# PIC.net
KiCad netlist of a schematic drawn in Altium Designer
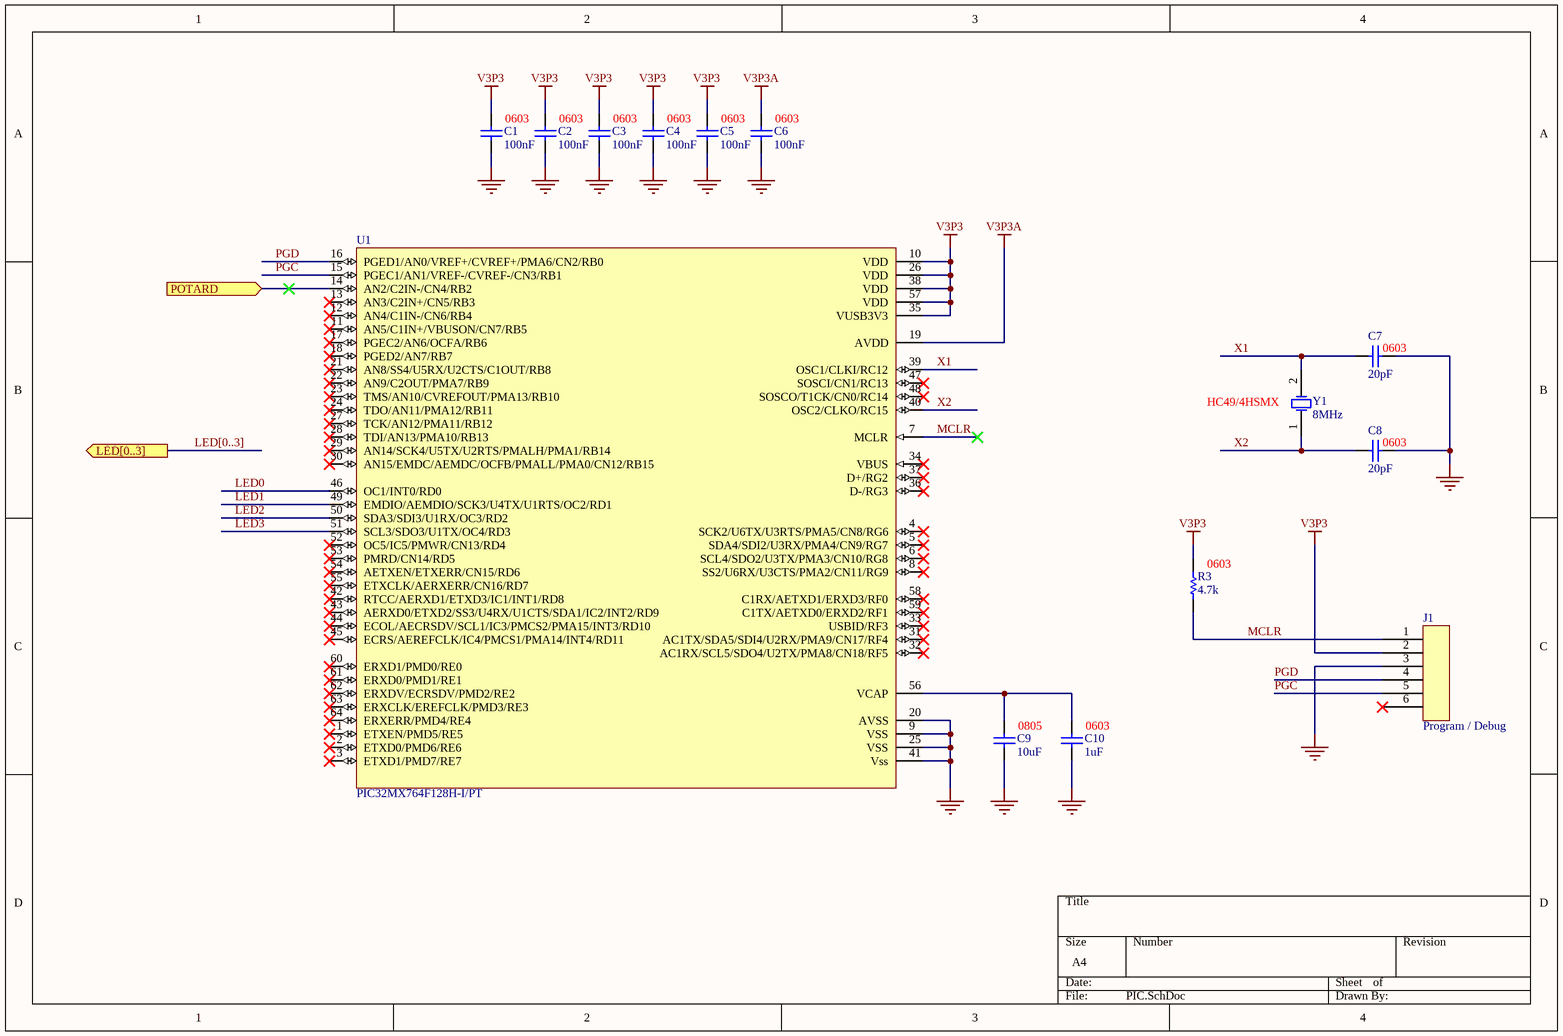
[diagram p0: PIC.SchDoc]

(export (version "E")
  (design (tool "Eeschema 10.0.6"))
  (components
    (comp (ref "C1")
      (value "100nF")
      (footprint "0603")
      (description "Capacitor")
      (fields (field (name "PUBLISHER") "Altium Limited"))
      (libsource (lib "Miscellaneous Devices") (part "Cap"))
    )
    (comp (ref "C2")
      (value "100nF")
      (footprint "0603")
      (description "Capacitor")
      (fields (field (name "PUBLISHER") "Altium Limited"))
      (libsource (lib "Miscellaneous Devices") (part "Cap"))
    )
    (comp (ref "C3")
      (value "100nF")
      (footprint "0603")
      (description "Capacitor")
      (fields (field (name "PUBLISHER") "Altium Limited"))
      (libsource (lib "Miscellaneous Devices") (part "Cap"))
    )
    (comp (ref "C4")
      (value "100nF")
      (footprint "0603")
      (description "Capacitor")
      (fields (field (name "PUBLISHER") "Altium Limited"))
      (libsource (lib "Miscellaneous Devices") (part "Cap"))
    )
    (comp (ref "C5")
      (value "100nF")
      (footprint "0603")
      (description "Capacitor")
      (fields (field (name "PUBLISHER") "Altium Limited"))
      (libsource (lib "Miscellaneous Devices") (part "Cap"))
    )
    (comp (ref "C6")
      (value "100nF")
      (footprint "0603")
      (description "Capacitor")
      (fields (field (name "PUBLISHER") "Altium Limited"))
      (libsource (lib "Miscellaneous Devices") (part "Cap"))
    )
    (comp (ref "C7")
      (value "20pF")
      (footprint "0603")
      (description "Capacitor")
      (fields (field (name "PUBLISHER") "Altium Limited"))
      (libsource (lib "Miscellaneous Devices") (part "Cap"))
    )
    (comp (ref "C8")
      (value "20pF")
      (footprint "0603")
      (description "Capacitor")
      (fields (field (name "PUBLISHER") "Altium Limited"))
      (libsource (lib "Miscellaneous Devices") (part "Cap"))
    )
    (comp (ref "C9")
      (value "10uF")
      (footprint "0805")
      (description "Capacitor")
      (fields (field (name "PUBLISHER") "Altium Limited"))
      (libsource (lib "Miscellaneous Devices") (part "Cap"))
    )
    (comp (ref "C10")
      (value "1uF")
      (footprint "0603")
      (description "Capacitor")
      (fields (field (name "PUBLISHER") "Altium Limited"))
      (libsource (lib "Miscellaneous Devices") (part "Cap"))
    )
    (comp (ref "J1")
      (value "Program / Debug")
      (footprint "TP2_PcbLib:RJ12_90")
      (description "RJ11")
      (libsource (lib "Program_Debug") (part "Program / Debug"))
    )
    (comp (ref "R3")
      (value "4.7k")
      (footprint "0603")
      (description "Resistor")
      (fields (field (name "PUBLISHER") "Altium Limited"))
      (libsource (lib "Miscellaneous Devices") (part "Res1"))
    )
    (comp (ref "U1")
      (value "PIC32MX764F128H-I/PT")
      (footprint "TP2_PcbLib:QFP50P1200X1200X120-64")
      (description "PIC32MX764F128H")
      (libsource (lib "TP2") (part "PIC32MX764F128H-I/PT"))
    )
    (comp (ref "Y1")
      (value "8MHz")
      (footprint "HC49/4HSMX")
      (description "Crystal Oscillator")
      (fields (field (name "PUBLISHER") "Altium Limited"))
      (libsource (lib "Miscellaneous Devices") (part "XTAL"))
    )
  )
  (nets
    (net (code "1") (name "/LED0") (class "Default")
      (node (ref "U1") (pin "46") (pinfunction "OC1/INT0/RD0_46") (pintype "bidirectional"))
    )
    (net (code "2") (name "/LED1") (class "Default")
      (node (ref "U1") (pin "49") (pinfunction "EMDIO/AEMDIO/SCK3/U4TX/U1RTS/OC2/RD1_49") (pintype "bidirectional"))
    )
    (net (code "3") (name "/LED2") (class "Default")
      (node (ref "U1") (pin "50") (pinfunction "SDA3/SDI3/U1RX/OC3/RD2_50") (pintype "bidirectional"))
    )
    (net (code "4") (name "/LED3") (class "Default")
      (node (ref "U1") (pin "51") (pinfunction "SCL3/SDO3/U1TX/OC4/RD3_51") (pintype "bidirectional"))
    )
    (net (code "6") (name "/MCLR") (class "Default")
      (node (ref "J1") (pin "1") (pinfunction "*_1") (pintype "passive"))
      (node (ref "R3") (pin "2") (pinfunction "2_2") (pintype "passive"))
      (node (ref "U1") (pin "7") (pinfunction "MCLR_7") (pintype "input"))
    )
    (net (code "7") (name "/PGC") (class "Default")
      (node (ref "J1") (pin "5") (pinfunction "5_5") (pintype "passive"))
      (node (ref "U1") (pin "15") (pinfunction "PGEC1/AN1/VREF-/CVREF-/CN3/RB1_15") (pintype "bidirectional"))
    )
    (net (code "8") (name "/PGD") (class "Default")
      (node (ref "J1") (pin "4") (pinfunction "4_4") (pintype "passive"))
      (node (ref "U1") (pin "16") (pinfunction "PGED1/AN0/VREF+/CVREF+/PMA6/CN2/RB0_16") (pintype "bidirectional"))
    )
    (net (code "9") (name "/POTARD") (class "Default")
      (node (ref "U1") (pin "14") (pinfunction "AN2/C2IN-/CN4/RB2_14") (pintype "bidirectional+no_connect"))
    )
    (net (code "10") (name "/X1") (class "Default")
      (node (ref "C7") (pin "2") (pinfunction "2_2") (pintype "passive"))
      (node (ref "U1") (pin "39") (pinfunction "OSC1/CLKI/RC12_39") (pintype "bidirectional"))
      (node (ref "Y1") (pin "2") (pinfunction "OSC2_2") (pintype "passive"))
    )
    (net (code "11") (name "/X2") (class "Default")
      (node (ref "C8") (pin "2") (pinfunction "2_2") (pintype "passive"))
      (node (ref "U1") (pin "40") (pinfunction "OSC2/CLKO/RC15_40") (pintype "bidirectional"))
      (node (ref "Y1") (pin "1") (pinfunction "OSC1_1") (pintype "passive"))
    )
    (net (code "12") (name "GND") (class "Default")
      (node (ref "C1") (pin "1") (pinfunction "1_1") (pintype "passive"))
      (node (ref "C10") (pin "1") (pinfunction "1_1") (pintype "passive"))
      (node (ref "C2") (pin "1") (pinfunction "1_1") (pintype "passive"))
      (node (ref "C3") (pin "1") (pinfunction "1_1") (pintype "passive"))
      (node (ref "C4") (pin "1") (pinfunction "1_1") (pintype "passive"))
      (node (ref "C5") (pin "1") (pinfunction "1_1") (pintype "passive"))
      (node (ref "C6") (pin "1") (pinfunction "1_1") (pintype "passive"))
      (node (ref "C7") (pin "1") (pinfunction "1_1") (pintype "passive"))
      (node (ref "C8") (pin "1") (pinfunction "1_1") (pintype "passive"))
      (node (ref "C9") (pin "1") (pinfunction "1_1") (pintype "passive"))
      (node (ref "J1") (pin "3") (pinfunction "3_3") (pintype "passive"))
      (node (ref "U1") (pin "20") (pinfunction "AVSS_20") (pintype "passive"))
      (node (ref "U1") (pin "25") (pinfunction "VSS_25") (pintype "passive"))
      (node (ref "U1") (pin "41") (pinfunction "Vss_41") (pintype "passive"))
      (node (ref "U1") (pin "9") (pinfunction "VSS_9") (pintype "passive"))
    )
    (net (code "13") (name "Net-(U1-VCAP)") (class "Default")
      (node (ref "C10") (pin "2") (pinfunction "2_2") (pintype "passive"))
      (node (ref "C9") (pin "2") (pinfunction "2_2") (pintype "passive"))
      (node (ref "U1") (pin "56") (pinfunction "VCAP_56") (pintype "passive"))
    )
    (net (code "14") (name "V3P3") (class "Default")
      (node (ref "C1") (pin "2") (pinfunction "2_2") (pintype "passive"))
      (node (ref "C2") (pin "2") (pinfunction "2_2") (pintype "passive"))
      (node (ref "C3") (pin "2") (pinfunction "2_2") (pintype "passive"))
      (node (ref "C4") (pin "2") (pinfunction "2_2") (pintype "passive"))
      (node (ref "C5") (pin "2") (pinfunction "2_2") (pintype "passive"))
      (node (ref "J1") (pin "2") (pinfunction "2_2") (pintype "passive"))
      (node (ref "R3") (pin "1") (pinfunction "1_1") (pintype "passive"))
      (node (ref "U1") (pin "10") (pinfunction "VDD_10") (pintype "passive"))
      (node (ref "U1") (pin "26") (pinfunction "VDD_26") (pintype "passive"))
      (node (ref "U1") (pin "35") (pinfunction "VUSB3V3_35") (pintype "passive"))
      (node (ref "U1") (pin "38") (pinfunction "VDD_38") (pintype "passive"))
      (node (ref "U1") (pin "57") (pinfunction "VDD_57") (pintype "passive"))
    )
    (net (code "15") (name "V3P3A") (class "Default")
      (node (ref "C6") (pin "2") (pinfunction "2_2") (pintype "passive"))
      (node (ref "U1") (pin "19") (pinfunction "AVDD_19") (pintype "passive"))
    )
    (net (code "16") (name "unconnected-(J1-Pad6)") (class "Default")
      (node (ref "J1") (pin "6") (pinfunction "6_6") (pintype "passive+no_connect"))
    )
    (net (code "17") (name "unconnected-(U1-AC1RX{slash}SCL5{slash}SDO4{slash}U2TX{slash}PMA8{slash}CN18{slash}RF5-Pad32)") (class "Default")
      (node (ref "U1") (pin "32") (pinfunction "AC1RX/SCL5/SDO4/U2TX/PMA8/CN18/RF5_32") (pintype "bidirectional+no_connect"))
    )
    (net (code "18") (name "unconnected-(U1-AC1TX{slash}SDA5{slash}SDI4{slash}U2RX{slash}PMA9{slash}CN17{slash}RF4-Pad31)") (class "Default")
      (node (ref "U1") (pin "31") (pinfunction "AC1TX/SDA5/SDI4/U2RX/PMA9/CN17/RF4_31") (pintype "bidirectional+no_connect"))
    )
    (net (code "19") (name "unconnected-(U1-AERXD0{slash}ETXD2{slash}SS3{slash}U4RX{slash}U1CTS{slash}SDA1{slash}IC2{slash}INT2{slash}RD9-Pad43)") (class "Default")
      (node (ref "U1") (pin "43") (pinfunction "AERXD0/ETXD2/SS3/U4RX/U1CTS/SDA1/IC2/INT2/RD9_43") (pintype "bidirectional+no_connect"))
    )
    (net (code "20") (name "unconnected-(U1-AETXEN{slash}ETXERR{slash}CN15{slash}RD6-Pad54)") (class "Default")
      (node (ref "U1") (pin "54") (pinfunction "AETXEN/ETXERR/CN15/RD6_54") (pintype "bidirectional+no_connect"))
    )
    (net (code "21") (name "unconnected-(U1-AN3{slash}C2IN+{slash}CN5{slash}RB3-Pad13)") (class "Default")
      (node (ref "U1") (pin "13") (pinfunction "AN3/C2IN+/CN5/RB3_13") (pintype "bidirectional+no_connect"))
    )
    (net (code "22") (name "unconnected-(U1-AN4{slash}C1IN-{slash}CN6{slash}RB4-Pad12)") (class "Default")
      (node (ref "U1") (pin "12") (pinfunction "AN4/C1IN-/CN6/RB4_12") (pintype "bidirectional+no_connect"))
    )
    (net (code "23") (name "unconnected-(U1-AN5{slash}C1IN+{slash}VBUSON{slash}CN7{slash}RB5-Pad11)") (class "Default")
      (node (ref "U1") (pin "11") (pinfunction "AN5/C1IN+/VBUSON/CN7/RB5_11") (pintype "bidirectional+no_connect"))
    )
    (net (code "24") (name "unconnected-(U1-AN8{slash}SS4{slash}U5RX{slash}U2CTS{slash}C1OUT{slash}RB8-Pad21)") (class "Default")
      (node (ref "U1") (pin "21") (pinfunction "AN8/SS4/U5RX/U2CTS/C1OUT/RB8_21") (pintype "bidirectional+no_connect"))
    )
    (net (code "25") (name "unconnected-(U1-AN9{slash}C2OUT{slash}PMA7{slash}RB9-Pad22)") (class "Default")
      (node (ref "U1") (pin "22") (pinfunction "AN9/C2OUT/PMA7/RB9_22") (pintype "bidirectional+no_connect"))
    )
    (net (code "26") (name "unconnected-(U1-AN14{slash}SCK4{slash}U5TX{slash}U2RTS{slash}PMALH{slash}PMA1{slash}RB14-Pad29)") (class "Default")
      (node (ref "U1") (pin "29") (pinfunction "AN14/SCK4/U5TX/U2RTS/PMALH/PMA1/RB14_29") (pintype "bidirectional+no_connect"))
    )
    (net (code "27") (name "unconnected-(U1-AN15{slash}EMDC{slash}AEMDC{slash}OCFB{slash}PMALL{slash}PMA0{slash}CN12{slash}RB15-Pad30)") (class "Default")
      (node (ref "U1") (pin "30") (pinfunction "AN15/EMDC/AEMDC/OCFB/PMALL/PMA0/CN12/RB15_30") (pintype "bidirectional+no_connect"))
    )
    (net (code "28") (name "unconnected-(U1-C1RX{slash}AETXD1{slash}ERXD3{slash}RF0-Pad58)") (class "Default")
      (node (ref "U1") (pin "58") (pinfunction "C1RX/AETXD1/ERXD3/RF0_58") (pintype "bidirectional+no_connect"))
    )
    (net (code "29") (name "unconnected-(U1-C1TX{slash}AETXD0{slash}ERXD2{slash}RF1-Pad59)") (class "Default")
      (node (ref "U1") (pin "59") (pinfunction "C1TX/AETXD0/ERXD2/RF1_59") (pintype "bidirectional+no_connect"))
    )
    (net (code "30") (name "unconnected-(U1-D+{slash}RG2-Pad37)") (class "Default")
      (node (ref "U1") (pin "37") (pinfunction "D+/RG2_37") (pintype "bidirectional+no_connect"))
    )
    (net (code "31") (name "unconnected-(U1-D-{slash}RG3-Pad36)") (class "Default")
      (node (ref "U1") (pin "36") (pinfunction "D-/RG3_36") (pintype "bidirectional+no_connect"))
    )
    (net (code "32") (name "unconnected-(U1-ECOL{slash}AECRSDV{slash}SCL1{slash}IC3{slash}PMCS2{slash}PMA15{slash}INT3{slash}RD10-Pad44)") (class "Default")
      (node (ref "U1") (pin "44") (pinfunction "ECOL/AECRSDV/SCL1/IC3/PMCS2/PMA15/INT3/RD10_44") (pintype "bidirectional+no_connect"))
    )
    (net (code "33") (name "unconnected-(U1-ECRS{slash}AEREFCLK{slash}IC4{slash}PMCS1{slash}PMA14{slash}INT4{slash}RD11-Pad45)") (class "Default")
      (node (ref "U1") (pin "45") (pinfunction "ECRS/AEREFCLK/IC4/PMCS1/PMA14/INT4/RD11_45") (pintype "bidirectional+no_connect"))
    )
    (net (code "34") (name "unconnected-(U1-ERXCLK{slash}EREFCLK{slash}PMD3{slash}RE3-Pad63)") (class "Default")
      (node (ref "U1") (pin "63") (pinfunction "ERXCLK/EREFCLK/PMD3/RE3_63") (pintype "bidirectional+no_connect"))
    )
    (net (code "35") (name "unconnected-(U1-ERXD0{slash}PMD1{slash}RE1-Pad61)") (class "Default")
      (node (ref "U1") (pin "61") (pinfunction "ERXD0/PMD1/RE1_61") (pintype "bidirectional+no_connect"))
    )
    (net (code "36") (name "unconnected-(U1-ERXD1{slash}PMD0{slash}RE0-Pad60)") (class "Default")
      (node (ref "U1") (pin "60") (pinfunction "ERXD1/PMD0/RE0_60") (pintype "bidirectional+no_connect"))
    )
    (net (code "37") (name "unconnected-(U1-ERXDV{slash}ECRSDV{slash}PMD2{slash}RE2-Pad62)") (class "Default")
      (node (ref "U1") (pin "62") (pinfunction "ERXDV/ECRSDV/PMD2/RE2_62") (pintype "bidirectional+no_connect"))
    )
    (net (code "38") (name "unconnected-(U1-ERXERR{slash}PMD4{slash}RE4-Pad64)") (class "Default")
      (node (ref "U1") (pin "64") (pinfunction "ERXERR/PMD4/RE4_64") (pintype "bidirectional+no_connect"))
    )
    (net (code "39") (name "unconnected-(U1-ETXCLK{slash}AERXERR{slash}CN16{slash}RD7-Pad55)") (class "Default")
      (node (ref "U1") (pin "55") (pinfunction "ETXCLK/AERXERR/CN16/RD7_55") (pintype "bidirectional+no_connect"))
    )
    (net (code "40") (name "unconnected-(U1-ETXD0{slash}PMD6{slash}RE6-Pad2)") (class "Default")
      (node (ref "U1") (pin "2") (pinfunction "ETXD0/PMD6/RE6_2") (pintype "bidirectional+no_connect"))
    )
    (net (code "41") (name "unconnected-(U1-ETXD1{slash}PMD7{slash}RE7-Pad3)") (class "Default")
      (node (ref "U1") (pin "3") (pinfunction "ETXD1/PMD7/RE7_3") (pintype "bidirectional+no_connect"))
    )
    (net (code "42") (name "unconnected-(U1-ETXEN{slash}PMD5{slash}RE5-Pad1)") (class "Default")
      (node (ref "U1") (pin "1") (pinfunction "ETXEN/PMD5/RE5_1") (pintype "bidirectional+no_connect"))
    )
    (net (code "43") (name "unconnected-(U1-OC5{slash}IC5{slash}PMWR{slash}CN13{slash}RD4-Pad52)") (class "Default")
      (node (ref "U1") (pin "52") (pinfunction "OC5/IC5/PMWR/CN13/RD4_52") (pintype "bidirectional+no_connect"))
    )
    (net (code "44") (name "unconnected-(U1-PGEC2{slash}AN6{slash}OCFA{slash}RB6-Pad17)") (class "Default")
      (node (ref "U1") (pin "17") (pinfunction "PGEC2/AN6/OCFA/RB6_17") (pintype "bidirectional+no_connect"))
    )
    (net (code "45") (name "unconnected-(U1-PGED2{slash}AN7{slash}RB7-Pad18)") (class "Default")
      (node (ref "U1") (pin "18") (pinfunction "PGED2/AN7/RB7_18") (pintype "bidirectional+no_connect"))
    )
    (net (code "46") (name "unconnected-(U1-PMRD{slash}CN14{slash}RD5-Pad53)") (class "Default")
      (node (ref "U1") (pin "53") (pinfunction "PMRD/CN14/RD5_53") (pintype "bidirectional+no_connect"))
    )
    (net (code "47") (name "unconnected-(U1-RTCC{slash}AERXD1{slash}ETXD3{slash}IC1{slash}INT1{slash}RD8-Pad42)") (class "Default")
      (node (ref "U1") (pin "42") (pinfunction "RTCC/AERXD1/ETXD3/IC1/INT1/RD8_42") (pintype "bidirectional+no_connect"))
    )
    (net (code "48") (name "unconnected-(U1-SCK2{slash}U6TX{slash}U3RTS{slash}PMA5{slash}CN8{slash}RG6-Pad4)") (class "Default")
      (node (ref "U1") (pin "4") (pinfunction "SCK2/U6TX/U3RTS/PMA5/CN8/RG6_4") (pintype "bidirectional+no_connect"))
    )
    (net (code "49") (name "unconnected-(U1-SCL4{slash}SDO2{slash}U3TX{slash}PMA3{slash}CN10{slash}RG8-Pad6)") (class "Default")
      (node (ref "U1") (pin "6") (pinfunction "SCL4/SDO2/U3TX/PMA3/CN10/RG8_6") (pintype "bidirectional+no_connect"))
    )
    (net (code "50") (name "unconnected-(U1-SDA4{slash}SDI2{slash}U3RX{slash}PMA4{slash}CN9{slash}RG7-Pad5)") (class "Default")
      (node (ref "U1") (pin "5") (pinfunction "SDA4/SDI2/U3RX/PMA4/CN9/RG7_5") (pintype "bidirectional+no_connect"))
    )
    (net (code "51") (name "unconnected-(U1-SOSCI{slash}CN1{slash}RC13-Pad47)") (class "Default")
      (node (ref "U1") (pin "47") (pinfunction "SOSCI/CN1/RC13_47") (pintype "bidirectional+no_connect"))
    )
    (net (code "52") (name "unconnected-(U1-SOSCO{slash}T1CK{slash}CN0{slash}RC14-Pad48)") (class "Default")
      (node (ref "U1") (pin "48") (pinfunction "SOSCO/T1CK/CN0/RC14_48") (pintype "bidirectional+no_connect"))
    )
    (net (code "53") (name "unconnected-(U1-SS2{slash}U6RX{slash}U3CTS{slash}PMA2{slash}CN11{slash}RG9-Pad8)") (class "Default")
      (node (ref "U1") (pin "8") (pinfunction "SS2/U6RX/U3CTS/PMA2/CN11/RG9_8") (pintype "bidirectional+no_connect"))
    )
    (net (code "54") (name "unconnected-(U1-TCK{slash}AN12{slash}PMA11{slash}RB12-Pad27)") (class "Default")
      (node (ref "U1") (pin "27") (pinfunction "TCK/AN12/PMA11/RB12_27") (pintype "bidirectional+no_connect"))
    )
    (net (code "55") (name "unconnected-(U1-TDI{slash}AN13{slash}PMA10{slash}RB13-Pad28)") (class "Default")
      (node (ref "U1") (pin "28") (pinfunction "TDI/AN13/PMA10/RB13_28") (pintype "bidirectional+no_connect"))
    )
    (net (code "56") (name "unconnected-(U1-TDO{slash}AN11{slash}PMA12{slash}RB11-Pad24)") (class "Default")
      (node (ref "U1") (pin "24") (pinfunction "TDO/AN11/PMA12/RB11_24") (pintype "bidirectional+no_connect"))
    )
    (net (code "57") (name "unconnected-(U1-TMS{slash}AN10{slash}CVREFOUT{slash}PMA13{slash}RB10-Pad23)") (class "Default")
      (node (ref "U1") (pin "23") (pinfunction "TMS/AN10/CVREFOUT/PMA13/RB10_23") (pintype "bidirectional+no_connect"))
    )
    (net (code "58") (name "unconnected-(U1-USBID{slash}RF3-Pad33)") (class "Default")
      (node (ref "U1") (pin "33") (pinfunction "USBID/RF3_33") (pintype "bidirectional+no_connect"))
    )
    (net (code "59") (name "unconnected-(U1-VBUS-Pad34)") (class "Default")
      (node (ref "U1") (pin "34") (pinfunction "VBUS_34") (pintype "input+no_connect"))
    )
  )
)
